# Proiect_TSC_v93.net
KiCad netlist of a schematic drawn in EAGLE
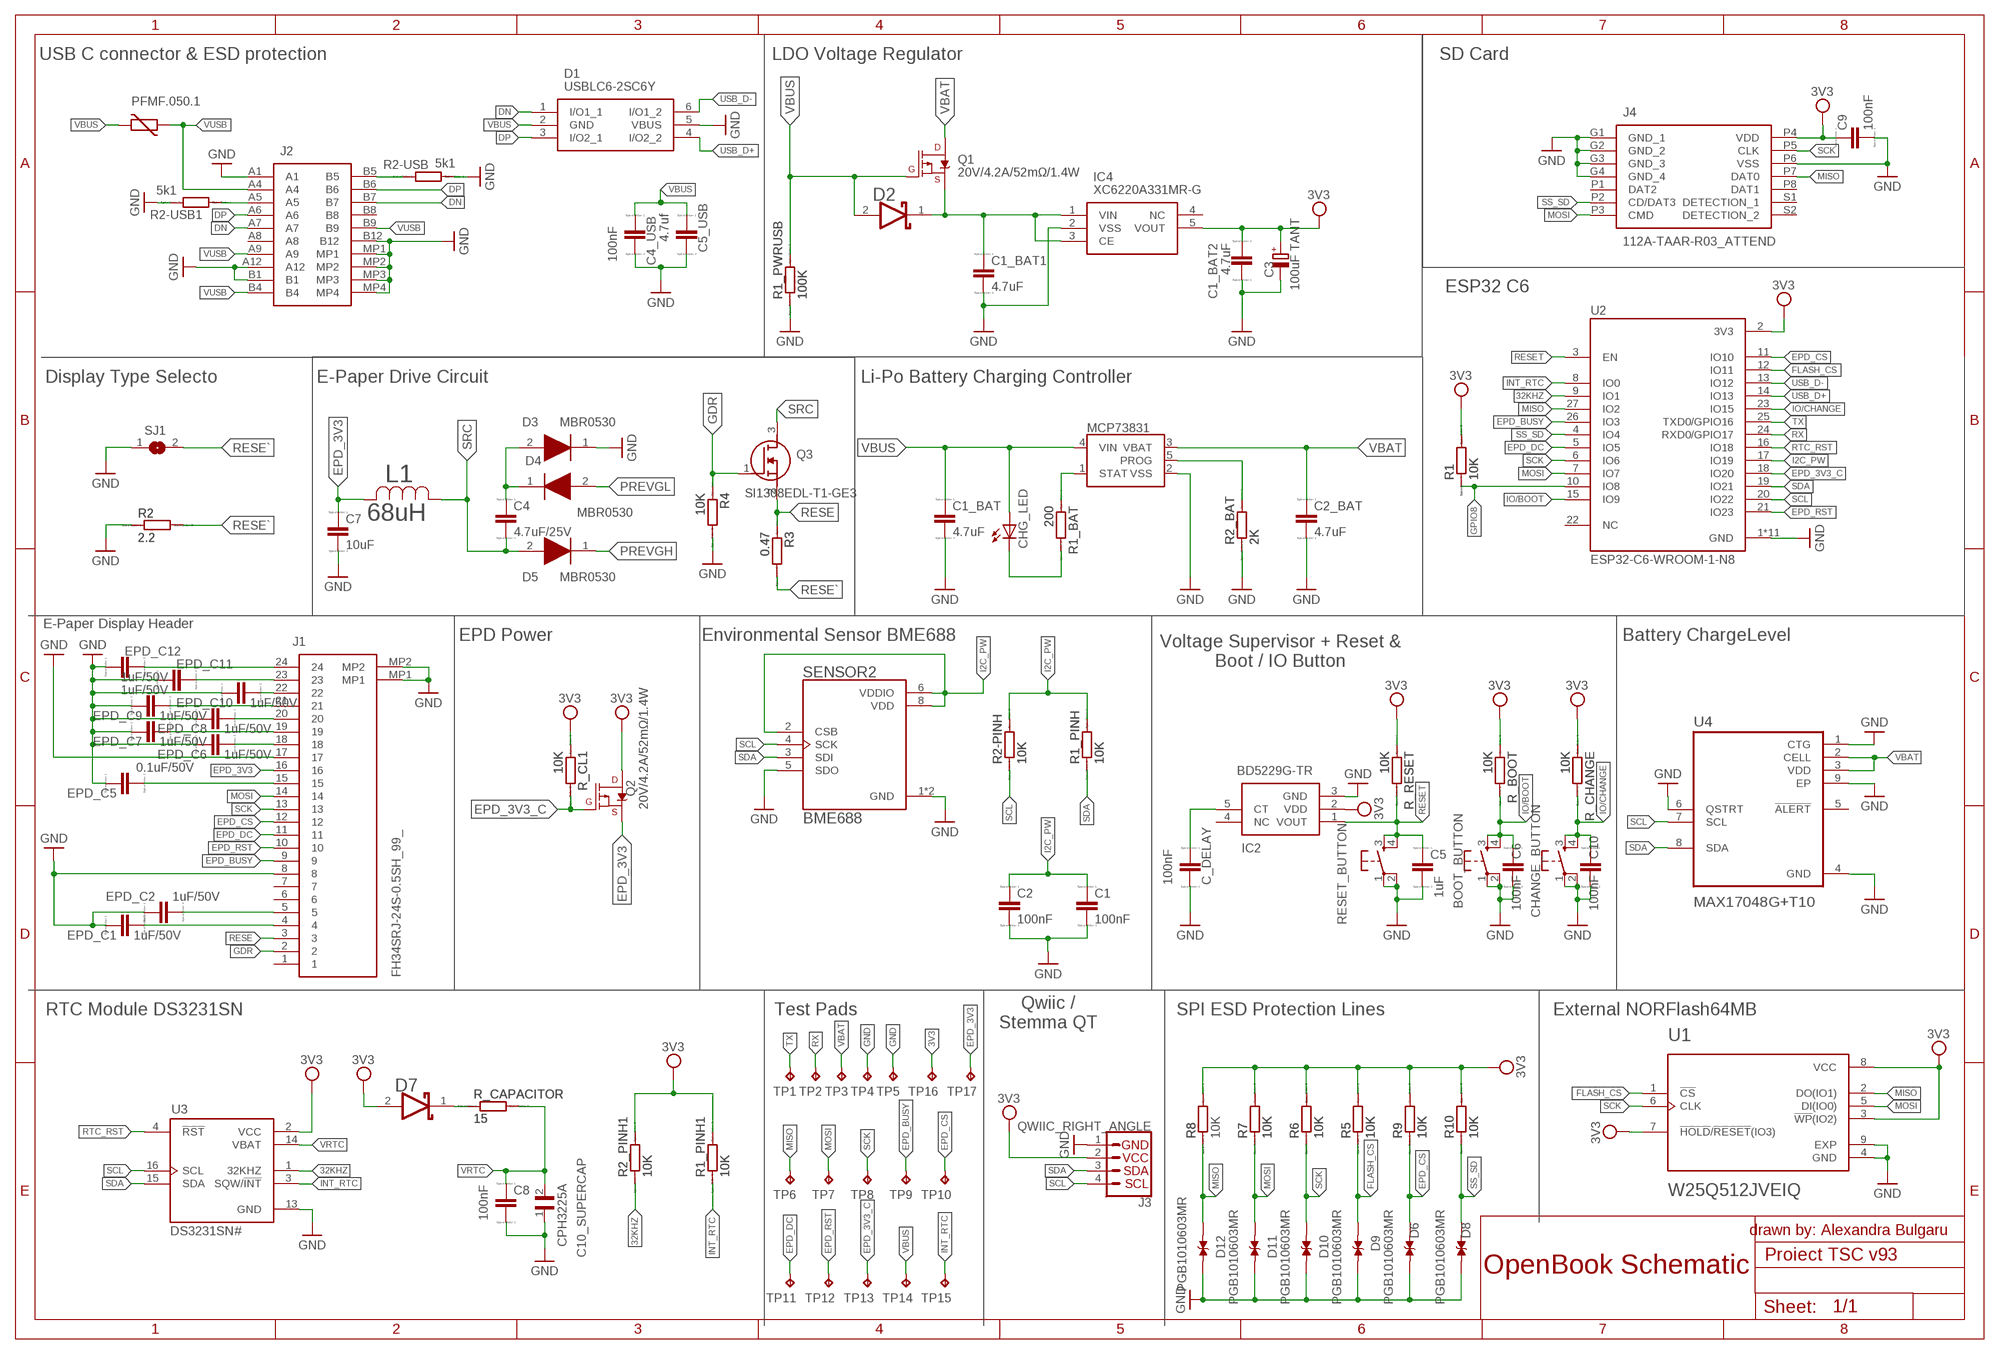
[diagram p0: schematic, sheet 1]

(export (version "E")
  (design (tool "Eeschema 10.0.6"))
  (components
    (comp (ref "BOOT_BUTTON")
      (value "BUTTON_CUSYOMV1")
      (footprint "eagle-import:MYBUTTON")
      (libsource (lib "eagle-import") (part "BUTTON_CUSYOMV1"))
    )
    (comp (ref "C1")
      (value "100nF")
      (footprint "eagle-import:EAGLE-LTSPICE_C0402")
      (libsource (lib "eagle-import") (part "EAGLE-LTSPICE_CC0402"))
    )
    (comp (ref "C1_BAT")
      (value "4.7uF")
      (footprint "eagle-import:EAGLE-LTSPICE_C0402")
      (libsource (lib "eagle-import") (part "EAGLE-LTSPICE_CC0402"))
    )
    (comp (ref "C1_BAT1")
      (value "4.7uF")
      (footprint "eagle-import:EAGLE-LTSPICE_C0402")
      (libsource (lib "eagle-import") (part "EAGLE-LTSPICE_CC0402"))
    )
    (comp (ref "C1_BAT2")
      (value "4.7uF")
      (footprint "eagle-import:EAGLE-LTSPICE_C0402")
      (libsource (lib "eagle-import") (part "EAGLE-LTSPICE_CC0402"))
    )
    (comp (ref "C2")
      (value "100nF")
      (footprint "eagle-import:EAGLE-LTSPICE_C0402")
      (libsource (lib "eagle-import") (part "EAGLE-LTSPICE_CC0402"))
    )
    (comp (ref "C2_BAT")
      (value "4.7uF")
      (footprint "eagle-import:EAGLE-LTSPICE_C0402")
      (libsource (lib "eagle-import") (part "EAGLE-LTSPICE_CC0402"))
    )
    (comp (ref "C3")
      (value "100uF TANT")
      (footprint "eagle-import:RCL_CT3528")
      (libsource (lib "eagle-import") (part "RCL_CPOL-EUCT3528"))
    )
    (comp (ref "C4")
      (value "4.7uF/25V")
      (footprint "eagle-import:EAGLE-LTSPICE_C0402")
      (libsource (lib "eagle-import") (part "EAGLE-LTSPICE_CC0402"))
    )
    (comp (ref "C4_USB")
      (value "100nF")
      (footprint "eagle-import:EAGLE-LTSPICE_C0402")
      (libsource (lib "eagle-import") (part "EAGLE-LTSPICE_CC0402"))
    )
    (comp (ref "C5")
      (value "1uF")
      (footprint "eagle-import:EAGLE-LTSPICE_C0402")
      (libsource (lib "eagle-import") (part "EAGLE-LTSPICE_CC0402"))
    )
    (comp (ref "C5_USB")
      (value "4.7uf")
      (footprint "eagle-import:EAGLE-LTSPICE_C0402")
      (libsource (lib "eagle-import") (part "EAGLE-LTSPICE_CC0402"))
    )
    (comp (ref "C6")
      (value "100nF")
      (footprint "eagle-import:EAGLE-LTSPICE_C0402")
      (libsource (lib "eagle-import") (part "EAGLE-LTSPICE_CC0402"))
    )
    (comp (ref "C7")
      (value "10uF")
      (footprint "eagle-import:EAGLE-LTSPICE_C0402")
      (libsource (lib "eagle-import") (part "EAGLE-LTSPICE_CC0402"))
    )
    (comp (ref "C8")
      (value "100nF")
      (footprint "eagle-import:EAGLE-LTSPICE_C0402")
      (libsource (lib "eagle-import") (part "EAGLE-LTSPICE_CC0402"))
    )
    (comp (ref "C9")
      (value "100nF")
      (footprint "eagle-import:ESP32_WROVER_EAGLE-LTSPICE_C0402")
      (libsource (lib "eagle-import") (part "ESP32_WROVER_EAGLE-LTSPICE_CC0402"))
    )
    (comp (ref "C10")
      (value "100nF")
      (footprint "eagle-import:EAGLE-LTSPICE_C0402")
      (libsource (lib "eagle-import") (part "EAGLE-LTSPICE_CC0402"))
    )
    (comp (ref "C10_SUPERCAP")
      (value "CPH3225A")
      (footprint "eagle-import:CAPCP3225X100N")
      (fields (field (name "MF") "Seiko Instruments"))
      (libsource (lib "eagle-import") (part "CPH3225A"))
    )
    (comp (ref "CHANGE_BUTTON")
      (value "BUTTON_CUSYOMV1")
      (footprint "eagle-import:MYBUTTON")
      (libsource (lib "eagle-import") (part "BUTTON_CUSYOMV1"))
    )
    (comp (ref "CHG_LED")
      (value "ADAFRUIT_LEDCHIP-LED0603")
      (footprint "eagle-import:ADAFRUIT_CHIP-LED0603")
      (libsource (lib "eagle-import") (part "ADAFRUIT_LEDCHIP-LED0603"))
    )
    (comp (ref "C_DELAY")
      (value "100nF")
      (footprint "eagle-import:EAGLE-LTSPICE_C0402")
      (libsource (lib "eagle-import") (part "EAGLE-LTSPICE_CC0402"))
    )
    (comp (ref "D1")
      (value "USBLC6-2SC6Y")
      (footprint "eagle-import:SOT95P280X145-6N")
      (fields (field (name "MF") "STMicroelectronics"))
      (libsource (lib "eagle-import") (part "USBLC6-2SC6Y"))
    )
    (comp (ref "D2")
      (value "ESP32_WROVER_AVX---SD0805S020S1R0_AVX_SD0805S020S1R0_0_0AVX_SD0805S020S1R0_0_0")
      (footprint "eagle-import:ESP32_WROVER_AVX---SD0805S020S1R0_AVX_SD0805S020S1R0_0")
      (fields
        (field (name "DIGIKEY_PART_NUMBER") "478-7800-1-ND")
        (field (name "MF") "AVX")
        (field (name "MOUSER_PART_NUMBER") "581-SD0805S020S1R0")
      )
      (libsource (lib "eagle-import") (part "ESP32_WROVER_AVX---SD0805S020S1R0_AVX_SD0805S020S1R0_0_0AVX_SD0805S020S1R0_0_0"))
    )
    (comp (ref "D3")
      (value "MBR0530")
      (footprint "eagle-import:SOD3716X135N")
      (fields (field (name "MF") "ON Semiconductor"))
      (libsource (lib "eagle-import") (part "MBR0530"))
    )
    (comp (ref "D4")
      (value "MBR0530")
      (footprint "eagle-import:SOD3716X135N")
      (fields (field (name "MF") "ON Semiconductor"))
      (libsource (lib "eagle-import") (part "MBR0530"))
    )
    (comp (ref "D5")
      (value "MBR0530")
      (footprint "eagle-import:SOD3716X135N")
      (fields (field (name "MF") "ON Semiconductor"))
      (libsource (lib "eagle-import") (part "MBR0530"))
    )
    (comp (ref "D6")
      (value "PGB1010603MR")
      (footprint "eagle-import:DIOC1608X36N")
      (fields (field (name "MF") "Littelfuse Inc."))
      (libsource (lib "eagle-import") (part "PGB1010603MR"))
    )
    (comp (ref "D7")
      (value "ESP32_WROVER_AVX---SD0805S020S1R0_AVX_SD0805S020S1R0_0_0AVX_SD0805S020S1R0_0_0")
      (footprint "eagle-import:ESP32_WROVER_AVX---SD0805S020S1R0_AVX_SD0805S020S1R0_0")
      (fields
        (field (name "DIGIKEY_PART_NUMBER") "478-7800-1-ND")
        (field (name "MF") "AVX")
        (field (name "MOUSER_PART_NUMBER") "581-SD0805S020S1R0")
      )
      (libsource (lib "eagle-import") (part "ESP32_WROVER_AVX---SD0805S020S1R0_AVX_SD0805S020S1R0_0_0AVX_SD0805S020S1R0_0_0"))
    )
    (comp (ref "D8")
      (value "PGB1010603MR")
      (footprint "eagle-import:DIOC1608X36N")
      (fields (field (name "MF") "Littelfuse Inc."))
      (libsource (lib "eagle-import") (part "PGB1010603MR"))
    )
    (comp (ref "D9")
      (value "PGB1010603MR")
      (footprint "eagle-import:DIOC1608X36N")
      (fields (field (name "MF") "Littelfuse Inc."))
      (libsource (lib "eagle-import") (part "PGB1010603MR"))
    )
    (comp (ref "D10")
      (value "PGB1010603MR")
      (footprint "eagle-import:DIOC1608X36N")
      (fields (field (name "MF") "Littelfuse Inc."))
      (libsource (lib "eagle-import") (part "PGB1010603MR"))
    )
    (comp (ref "D11")
      (value "PGB1010603MR")
      (footprint "eagle-import:DIOC1608X36N")
      (fields (field (name "MF") "Littelfuse Inc."))
      (libsource (lib "eagle-import") (part "PGB1010603MR"))
    )
    (comp (ref "D12")
      (value "PGB1010603MR")
      (footprint "eagle-import:DIOC1608X36N")
      (fields (field (name "MF") "Littelfuse Inc."))
      (libsource (lib "eagle-import") (part "PGB1010603MR"))
    )
    (comp (ref "EPD_C1")
      (value "1uF/50V")
      (footprint "eagle-import:EAGLE-LTSPICE_C0402")
      (libsource (lib "eagle-import") (part "EAGLE-LTSPICE_CC0402"))
    )
    (comp (ref "EPD_C2")
      (value "1uF/50V")
      (footprint "eagle-import:EAGLE-LTSPICE_C0402")
      (libsource (lib "eagle-import") (part "EAGLE-LTSPICE_CC0402"))
    )
    (comp (ref "EPD_C5")
      (value "0.1uF/50V")
      (footprint "eagle-import:EAGLE-LTSPICE_C0402")
      (libsource (lib "eagle-import") (part "EAGLE-LTSPICE_CC0402"))
    )
    (comp (ref "EPD_C6")
      (value "1uF/50V")
      (footprint "eagle-import:EAGLE-LTSPICE_C0402")
      (libsource (lib "eagle-import") (part "EAGLE-LTSPICE_CC0402"))
    )
    (comp (ref "EPD_C7")
      (value "1uF/50V")
      (footprint "eagle-import:EAGLE-LTSPICE_C0402")
      (libsource (lib "eagle-import") (part "EAGLE-LTSPICE_CC0402"))
    )
    (comp (ref "EPD_C8")
      (value "1uF/50V")
      (footprint "eagle-import:EAGLE-LTSPICE_C0402")
      (libsource (lib "eagle-import") (part "EAGLE-LTSPICE_CC0402"))
    )
    (comp (ref "EPD_C9")
      (value "1uF/50V")
      (footprint "eagle-import:EAGLE-LTSPICE_C0402")
      (libsource (lib "eagle-import") (part "EAGLE-LTSPICE_CC0402"))
    )
    (comp (ref "EPD_C10")
      (value "1uF/50V")
      (footprint "eagle-import:EAGLE-LTSPICE_C0402")
      (libsource (lib "eagle-import") (part "EAGLE-LTSPICE_CC0402"))
    )
    (comp (ref "EPD_C11")
      (value "1uF/50V")
      (footprint "eagle-import:EAGLE-LTSPICE_C0402")
      (libsource (lib "eagle-import") (part "EAGLE-LTSPICE_CC0402"))
    )
    (comp (ref "EPD_C12")
      (value "1uF/50V")
      (footprint "eagle-import:EAGLE-LTSPICE_C0402")
      (libsource (lib "eagle-import") (part "EAGLE-LTSPICE_CC0402"))
    )
    (comp (ref "IC2")
      (value "BD5229G-TR")
      (footprint "eagle-import:SOT95P280X125-5N")
      (fields (field (name "MOUSER_PART_NUMBER") "755-BD5229G-TR"))
      (libsource (lib "eagle-import") (part "BD5229G-TR"))
    )
    (comp (ref "IC4")
      (value "XC6220A331MR-G")
      (footprint "eagle-import:SOT95P280X120-5N")
      (fields (field (name "MOUSER_PART_NUMBER") "865-XC6220A331MR-G"))
      (libsource (lib "eagle-import") (part "XC6220A331MR-G"))
    )
    (comp (ref "J1")
      (value "FH34SRJ-24S-0.5SH_99_")
      (footprint "eagle-import:FH34SRJ24S05SH99")
      (fields
        (field (name "MANUFACTURER_PART_NUMBER") "FH34SRJ-24S-0.5SH(99)")
        (field (name "MOUSER_PART_NUMBER") "798-FH34SRJ24S05SH99")
      )
      (libsource (lib "eagle-import") (part "FH34SRJ-24S-0.5SH_99_"))
    )
    (comp (ref "J2")
      (value "SAMACSYS_PARTS_USB4110-GF-A")
      (footprint "eagle-import:SAMACSYS_PARTS_USB4110GFA")
      (fields
        (field (name "MANUFACTURER_PART_NUMBER") "USB4110-GF-A")
        (field (name "MOUSER_PART_NUMBER") "640-USB4110-GF-A")
      )
      (libsource (lib "eagle-import") (part "SAMACSYS_PARTS_USB4110-GF-A"))
    )
    (comp (ref "J3")
      (value "QWIIC_RIGHT_ANGLE")
      (footprint "eagle-import:JST04_1MM_RA")
      (libsource (lib "eagle-import") (part "QWIIC_CONNECTORJS-1MM"))
    )
    (comp (ref "J4")
      (value "112A-TAAR-R03_ATTEND")
      (footprint "eagle-import:112ATAARR03ATTEND")
      (fields (field (name "MANUFACTURER_PART_NUMBER") "112A-TAAR-R03 ATTEND"))
      (libsource (lib "eagle-import") (part "112A-TAAR-R03_ATTEND"))
    )
    (comp (ref "L1")
      (value "68uH")
      (footprint "eagle-import:IND_4828-WE-TPC_WRE")
      (fields
        (field (name "MANUFACTURER_PART_NUMBER") "744043680")
        (field (name "COPYRIGHT") "Copyright (C) 2024 Ultra Librarian. All rights reserved.")
      )
      (libsource (lib "eagle-import") (part "744043680IND_4828-WE-TPC_WRE"))
    )
    (comp (ref "MCP73831")
      (value "ESP32_WROVER_SPARKFUN-IC-POWER_MCP73831")
      (footprint "eagle-import:ESP32_WROVER_SPARKFUN-IC-POWER_SOT23-5")
      (libsource (lib "eagle-import") (part "ESP32_WROVER_SPARKFUN-IC-POWER_MCP73831"))
    )
    (comp (ref "PFMF.050.1")
      (value "ESP32C6_VARISTORCN1812")
      (footprint "eagle-import:ESP32C6_VARISTOR_CT_CN1812")
      (libsource (lib "eagle-import") (part "ESP32C6_VARISTORCN1812"))
    )
    (comp (ref "Q1")
      (value "20V/4.2A/52mΩ/1.4W")
      (footprint "eagle-import:ESP32_WROVER_SPARKFUN-DISCRETESEMI_SOT23-3")
      (libsource (lib "eagle-import") (part "ESP32_WROVER_SPARKFUN-DISCRETESEMI_MOSFET_PCH-DMG2305UX-7"))
    )
    (comp (ref "Q2")
      (value "20V/4.2A/52mΩ/1.4W")
      (footprint "eagle-import:ESP32_WROVER_SPARKFUN-DISCRETESEMI_SOT23-3")
      (libsource (lib "eagle-import") (part "ESP32_WROVER_SPARKFUN-DISCRETESEMI_MOSFET_PCH-DMG2305UX-7"))
    )
    (comp (ref "Q3")
      (value "SI1308EDL-T1-GE3")
      (footprint "eagle-import:SOT65P210X110-3N")
      (fields (field (name "MF") "Vishay Siliconix"))
      (libsource (lib "eagle-import") (part "SI1308EDL-T1-GE3"))
    )
    (comp (ref "R1")
      (value "10K")
      (footprint "eagle-import:ESP32_WROVER_EAGLE-LTSPICE_R0402")
      (libsource (lib "eagle-import") (part "ESP32_WROVER_EAGLE-LTSPICE_RR0402"))
    )
    (comp (ref "R1_BAT")
      (value "200")
      (footprint "eagle-import:ESP32_WROVER_EAGLE-LTSPICE_R0402")
      (libsource (lib "eagle-import") (part "ESP32_WROVER_EAGLE-LTSPICE_RR0402"))
    )
    (comp (ref "R1_PINH")
      (value "10K")
      (footprint "eagle-import:ESP32_WROVER_EAGLE-LTSPICE_R0402")
      (libsource (lib "eagle-import") (part "ESP32_WROVER_EAGLE-LTSPICE_RR0402"))
    )
    (comp (ref "R1_PINH1")
      (value "10K")
      (footprint "eagle-import:ESP32_WROVER_EAGLE-LTSPICE_R0402")
      (libsource (lib "eagle-import") (part "ESP32_WROVER_EAGLE-LTSPICE_RR0402"))
    )
    (comp (ref "R1_PWRUSB")
      (value "100K")
      (footprint "eagle-import:ESP32_WROVER_EAGLE-LTSPICE_R0402")
      (libsource (lib "eagle-import") (part "ESP32_WROVER_EAGLE-LTSPICE_RR0402"))
    )
    (comp (ref "R2")
      (value "2.2")
      (footprint "eagle-import:ESP32_WROVER_EAGLE-LTSPICE_R0402")
      (libsource (lib "eagle-import") (part "ESP32_WROVER_EAGLE-LTSPICE_RR0402"))
    )
    (comp (ref "R2-PINH")
      (value "10K")
      (footprint "eagle-import:ESP32_WROVER_EAGLE-LTSPICE_R0402")
      (libsource (lib "eagle-import") (part "ESP32_WROVER_EAGLE-LTSPICE_RR0402"))
    )
    (comp (ref "R2-USB")
      (value "5k1")
      (footprint "eagle-import:ESP32_WROVER_EAGLE-LTSPICE_R0402")
      (libsource (lib "eagle-import") (part "ESP32_WROVER_EAGLE-LTSPICE_RR0402"))
    )
    (comp (ref "R2-USB1")
      (value "5k1")
      (footprint "eagle-import:ESP32_WROVER_EAGLE-LTSPICE_R0402")
      (libsource (lib "eagle-import") (part "ESP32_WROVER_EAGLE-LTSPICE_RR0402"))
    )
    (comp (ref "R2_BAT")
      (value "2K")
      (footprint "eagle-import:ESP32_WROVER_EAGLE-LTSPICE_R0402")
      (libsource (lib "eagle-import") (part "ESP32_WROVER_EAGLE-LTSPICE_RR0402"))
    )
    (comp (ref "R2_PINH1")
      (value "10K")
      (footprint "eagle-import:ESP32_WROVER_EAGLE-LTSPICE_R0402")
      (libsource (lib "eagle-import") (part "ESP32_WROVER_EAGLE-LTSPICE_RR0402"))
    )
    (comp (ref "R3")
      (value "0.47")
      (footprint "eagle-import:ESP32_WROVER_EAGLE-LTSPICE_R0402")
      (libsource (lib "eagle-import") (part "ESP32_WROVER_EAGLE-LTSPICE_RR0402"))
    )
    (comp (ref "R4")
      (value "10K")
      (footprint "eagle-import:ESP32_WROVER_EAGLE-LTSPICE_R0402")
      (libsource (lib "eagle-import") (part "ESP32_WROVER_EAGLE-LTSPICE_RR0402"))
    )
    (comp (ref "R5")
      (value "10K")
      (footprint "eagle-import:ESP32_WROVER_EAGLE-LTSPICE_R0402")
      (libsource (lib "eagle-import") (part "ESP32_WROVER_EAGLE-LTSPICE_RR0402"))
    )
    (comp (ref "R6")
      (value "10K")
      (footprint "eagle-import:ESP32_WROVER_EAGLE-LTSPICE_R0402")
      (libsource (lib "eagle-import") (part "ESP32_WROVER_EAGLE-LTSPICE_RR0402"))
    )
    (comp (ref "R7")
      (value "10K")
      (footprint "eagle-import:ESP32_WROVER_EAGLE-LTSPICE_R0402")
      (libsource (lib "eagle-import") (part "ESP32_WROVER_EAGLE-LTSPICE_RR0402"))
    )
    (comp (ref "R8")
      (value "10K")
      (footprint "eagle-import:ESP32_WROVER_EAGLE-LTSPICE_R0402")
      (libsource (lib "eagle-import") (part "ESP32_WROVER_EAGLE-LTSPICE_RR0402"))
    )
    (comp (ref "R9")
      (value "10K")
      (footprint "eagle-import:ESP32_WROVER_EAGLE-LTSPICE_R0402")
      (libsource (lib "eagle-import") (part "ESP32_WROVER_EAGLE-LTSPICE_RR0402"))
    )
    (comp (ref "R10")
      (value "10K")
      (footprint "eagle-import:ESP32_WROVER_EAGLE-LTSPICE_R0402")
      (libsource (lib "eagle-import") (part "ESP32_WROVER_EAGLE-LTSPICE_RR0402"))
    )
    (comp (ref "RESET_BUTTON")
      (value "BUTTON_CUSYOMV1")
      (footprint "eagle-import:MYBUTTON")
      (libsource (lib "eagle-import") (part "BUTTON_CUSYOMV1"))
    )
    (comp (ref "R_BOOT")
      (value "10K")
      (footprint "eagle-import:ESP32_WROVER_EAGLE-LTSPICE_R0402")
      (libsource (lib "eagle-import") (part "ESP32_WROVER_EAGLE-LTSPICE_RR0402"))
    )
    (comp (ref "R_CAPACITOR")
      (value "15")
      (footprint "eagle-import:ESP32_WROVER_EAGLE-LTSPICE_R0402")
      (libsource (lib "eagle-import") (part "ESP32_WROVER_EAGLE-LTSPICE_RR0402"))
    )
    (comp (ref "R_CHANGE")
      (value "10K")
      (footprint "eagle-import:ESP32_WROVER_EAGLE-LTSPICE_R0402")
      (libsource (lib "eagle-import") (part "ESP32_WROVER_EAGLE-LTSPICE_RR0402"))
    )
    (comp (ref "R_CL1")
      (value "10K")
      (footprint "eagle-import:ESP32_WROVER_EAGLE-LTSPICE_R0402")
      (libsource (lib "eagle-import") (part "ESP32_WROVER_EAGLE-LTSPICE_RR0402"))
    )
    (comp (ref "R_RESET")
      (value "10K")
      (footprint "eagle-import:ESP32_WROVER_EAGLE-LTSPICE_R0402")
      (libsource (lib "eagle-import") (part "ESP32_WROVER_EAGLE-LTSPICE_RR0402"))
    )
    (comp (ref "SENSOR2")
      (value "BME688")
      (footprint "eagle-import:ESP32_WROVER_BME680_PSON80P300X300X100-8N")
      (fields (field (name "MF") "Bosch Sensortec") (field (name "MP") "BME680"))
      (libsource (lib "eagle-import") (part "ESP32_WROVER_BME680_BME680"))
    )
    (comp (ref "SJ1") (value "SJ") (footprint "eagle-import:SJ") (libsource (lib "eagle-import") (part "SJ")))
    (comp (ref "TP1")
      (value "TPTP20R")
      (footprint "eagle-import:TP20R")
      (libsource (lib "eagle-import") (part "TPTP20R"))
    )
    (comp (ref "TP2")
      (value "TPTP20R")
      (footprint "eagle-import:TP20R")
      (libsource (lib "eagle-import") (part "TPTP20R"))
    )
    (comp (ref "TP3")
      (value "TPTP20R")
      (footprint "eagle-import:TP20R")
      (libsource (lib "eagle-import") (part "TPTP20R"))
    )
    (comp (ref "TP4")
      (value "TPTP20R")
      (footprint "eagle-import:TP20R")
      (libsource (lib "eagle-import") (part "TPTP20R"))
    )
    (comp (ref "TP5")
      (value "TPTP20R")
      (footprint "eagle-import:TP20R")
      (libsource (lib "eagle-import") (part "TPTP20R"))
    )
    (comp (ref "TP6")
      (value "TPTP20R")
      (footprint "eagle-import:TP20R")
      (libsource (lib "eagle-import") (part "TPTP20R"))
    )
    (comp (ref "TP7")
      (value "TPTP20R")
      (footprint "eagle-import:TP20R")
      (libsource (lib "eagle-import") (part "TPTP20R"))
    )
    (comp (ref "TP8")
      (value "TPTP20R")
      (footprint "eagle-import:TP20R")
      (libsource (lib "eagle-import") (part "TPTP20R"))
    )
    (comp (ref "TP9")
      (value "TPTP20R")
      (footprint "eagle-import:TP20R")
      (libsource (lib "eagle-import") (part "TPTP20R"))
    )
    (comp (ref "TP10")
      (value "TPTP20R")
      (footprint "eagle-import:TP20R")
      (libsource (lib "eagle-import") (part "TPTP20R"))
    )
    (comp (ref "TP11")
      (value "TPTP20R")
      (footprint "eagle-import:TP20R")
      (libsource (lib "eagle-import") (part "TPTP20R"))
    )
    (comp (ref "TP12")
      (value "TPTP20R")
      (footprint "eagle-import:TP20R")
      (libsource (lib "eagle-import") (part "TPTP20R"))
    )
    (comp (ref "TP13")
      (value "TPTP20R")
      (footprint "eagle-import:TP20R")
      (libsource (lib "eagle-import") (part "TPTP20R"))
    )
    (comp (ref "TP14")
      (value "TPTP20R")
      (footprint "eagle-import:TP20R")
      (libsource (lib "eagle-import") (part "TPTP20R"))
    )
    (comp (ref "TP15")
      (value "TPTP20R")
      (footprint "eagle-import:TP20R")
      (libsource (lib "eagle-import") (part "TPTP20R"))
    )
    (comp (ref "TP16")
      (value "TPTP20R")
      (footprint "eagle-import:TP20R")
      (libsource (lib "eagle-import") (part "TPTP20R"))
    )
    (comp (ref "TP17")
      (value "TPTP20R")
      (footprint "eagle-import:TP20R")
      (libsource (lib "eagle-import") (part "TPTP20R"))
    )
    (comp (ref "U1")
      (value "W25Q512JVEIQ")
      (footprint "eagle-import:SON127P600X800X80-9N")
      (fields (field (name "MF") "Winbond Electronics"))
      (libsource (lib "eagle-import") (part "W25Q512JVEIQ"))
    )
    (comp (ref "U2")
      (value "ESP32-C6-WROOM-1-N8")
      (footprint "eagle-import:XCVR_ESP32-C6-WROOM-1-N8")
      (fields (field (name "MF") "Espressif Systems"))
      (libsource (lib "eagle-import") (part "ESP32-C6-WROOM-1-N8"))
    )
    (comp (ref "U3")
      (value "DS3231SN#")
      (footprint "eagle-import:SOIC127P1032X265-16N")
      (fields (field (name "MF") "Analog Devices"))
      (libsource (lib "eagle-import") (part "DS3231SN#"))
    )
    (comp (ref "U4")
      (value "MAX17048G+T10")
      (footprint "eagle-import:SON50P200X200X80-9N")
      (fields (field (name "MF") "Analog Devices"))
      (libsource (lib "eagle-import") (part "MAX17048G+T10"))
    )
  )
  (nets
    (net (code "1") (name "3V3") (class "Default")
      (node (ref "C1_BAT2") (pin "2") (pinfunction "2_2") (pintype "passive"))
      (node (ref "C3") (pin "+") (pinfunction "+_+") (pintype "passive"))
      (node (ref "C9") (pin "1") (pinfunction "1_1") (pintype "passive"))
      (node (ref "D7") (pin "2") (pinfunction "ANODE_2") (pintype "bidirectional"))
      (node (ref "IC2") (pin "2") (pinfunction "VDD_2") (pintype "bidirectional"))
      (node (ref "IC4") (pin "5") (pinfunction "VOUT_5") (pintype "bidirectional"))
      (node (ref "J3") (pin "2") (pinfunction "2_2") (pintype "power_in"))
      (node (ref "J4") (pin "P4") (pinfunction "VDD_P4") (pintype "bidirectional"))
      (node (ref "Q2") (pin "3") (pinfunction "D_3") (pintype "bidirectional"))
      (node (ref "R1") (pin "2") (pinfunction "2_2") (pintype "passive"))
      (node (ref "R10") (pin "2") (pinfunction "2_2") (pintype "passive"))
      (node (ref "R1_PINH1") (pin "2") (pinfunction "2_2") (pintype "passive"))
      (node (ref "R2_PINH1") (pin "2") (pinfunction "2_2") (pintype "passive"))
      (node (ref "R5") (pin "2") (pinfunction "2_2") (pintype "passive"))
      (node (ref "R6") (pin "2") (pinfunction "2_2") (pintype "passive"))
      (node (ref "R7") (pin "2") (pinfunction "2_2") (pintype "passive"))
      (node (ref "R8") (pin "2") (pinfunction "2_2") (pintype "passive"))
      (node (ref "R9") (pin "2") (pinfunction "2_2") (pintype "passive"))
      (node (ref "R_BOOT") (pin "1") (pinfunction "1_1") (pintype "passive"))
      (node (ref "R_CHANGE") (pin "1") (pinfunction "1_1") (pintype "passive"))
      (node (ref "R_CL1") (pin "1") (pinfunction "1_1") (pintype "passive"))
      (node (ref "R_RESET") (pin "1") (pinfunction "1_1") (pintype "passive"))
      (node (ref "TP16") (pin "TP") (pinfunction "TP_TP") (pintype "input"))
      (node (ref "U1") (pin "3") (pinfunction "~{WP}(IO2)_3") (pintype "bidirectional"))
      (node (ref "U1") (pin "7") (pinfunction "~{HOLD}/~{RESET}(IO3)_7") (pintype "bidirectional"))
      (node (ref "U1") (pin "8") (pinfunction "VCC_8") (pintype "power_in"))
      (node (ref "U2") (pin "2") (pinfunction "3V3_2") (pintype "power_in"))
      (node (ref "U3") (pin "2") (pinfunction "VCC_2") (pintype "power_in"))
    )
    (net (code "2") (name "32KHZ") (class "Default")
      (node (ref "R2_PINH1") (pin "1") (pinfunction "1_1") (pintype "passive"))
      (node (ref "U2") (pin "9") (pinfunction "IO1_9") (pintype "bidirectional"))
      (node (ref "U3") (pin "1") (pinfunction "32KHZ_1") (pintype "output"))
    )
    (net (code "3") (name "DN") (class "Default")
      (node (ref "D1") (pin "1") (pinfunction "I/O1_1_1") (pintype "bidirectional"))
      (node (ref "J2") (pin "A7") (pinfunction "A7_A7") (pintype "bidirectional"))
      (node (ref "J2") (pin "B7") (pinfunction "B7_B7") (pintype "bidirectional"))
    )
    (net (code "4") (name "DP") (class "Default")
      (node (ref "D1") (pin "3") (pinfunction "I/O2_1_3") (pintype "bidirectional"))
      (node (ref "J2") (pin "A6") (pinfunction "A6_A6") (pintype "bidirectional"))
      (node (ref "J2") (pin "B6") (pinfunction "B6_B6") (pintype "bidirectional"))
    )
    (net (code "5") (name "EPD_3V3") (class "Default")
      (node (ref "C7") (pin "1") (pinfunction "1_1") (pintype "passive"))
      (node (ref "J1") (pin "16") (pinfunction "16_16") (pintype "bidirectional"))
      (node (ref "L1") (pin "2") (pinfunction "2_2") (pintype "passive"))
      (node (ref "Q2") (pin "2") (pinfunction "S_2") (pintype "bidirectional"))
      (node (ref "TP17") (pin "TP") (pinfunction "TP_TP") (pintype "input"))
    )
    (net (code "6") (name "EPD_3V3_C") (class "Default")
      (node (ref "Q2") (pin "1") (pinfunction "G_1") (pintype "bidirectional"))
      (node (ref "R_CL1") (pin "2") (pinfunction "2_2") (pintype "passive"))
      (node (ref "TP13") (pin "TP") (pinfunction "TP_TP") (pintype "input"))
      (node (ref "U2") (pin "18") (pinfunction "IO20_18") (pintype "bidirectional"))
    )
    (net (code "7") (name "EPD_BUSY") (class "Default")
      (node (ref "J1") (pin "9") (pinfunction "9_9") (pintype "bidirectional"))
      (node (ref "TP9") (pin "TP") (pinfunction "TP_TP") (pintype "input"))
      (node (ref "U2") (pin "26") (pinfunction "IO3_26") (pintype "bidirectional"))
    )
    (net (code "8") (name "EPD_CS") (class "Default")
      (node (ref "D6") (pin "1") (pinfunction "1_1") (pintype "passive"))
      (node (ref "J1") (pin "12") (pinfunction "12_12") (pintype "bidirectional"))
      (node (ref "R9") (pin "1") (pinfunction "1_1") (pintype "passive"))
      (node (ref "TP10") (pin "TP") (pinfunction "TP_TP") (pintype "input"))
      (node (ref "U2") (pin "11") (pinfunction "IO10_11") (pintype "bidirectional"))
    )
    (net (code "9") (name "EPD_DC") (class "Default")
      (node (ref "J1") (pin "11") (pinfunction "11_11") (pintype "bidirectional"))
      (node (ref "TP11") (pin "TP") (pinfunction "TP_TP") (pintype "input"))
      (node (ref "U2") (pin "5") (pinfunction "IO5_5") (pintype "bidirectional"))
    )
    (net (code "10") (name "EPD_RST") (class "Default")
      (node (ref "J1") (pin "10") (pinfunction "10_10") (pintype "bidirectional"))
      (node (ref "TP12") (pin "TP") (pinfunction "TP_TP") (pintype "input"))
      (node (ref "U2") (pin "21") (pinfunction "IO23_21") (pintype "bidirectional"))
    )
    (net (code "11") (name "FLASH_CS") (class "Default")
      (node (ref "D9") (pin "1") (pinfunction "1_1") (pintype "passive"))
      (node (ref "R5") (pin "1") (pinfunction "1_1") (pintype "passive"))
      (node (ref "U1") (pin "1") (pinfunction "~{CS}_1") (pintype "input"))
      (node (ref "U2") (pin "12") (pinfunction "IO11_12") (pintype "bidirectional"))
    )
    (net (code "12") (name "GDR") (class "Default")
      (node (ref "J1") (pin "2") (pinfunction "2_2") (pintype "bidirectional"))
      (node (ref "Q3") (pin "1") (pinfunction "G_1") (pintype "bidirectional"))
      (node (ref "R4") (pin "1") (pinfunction "1_1") (pintype "passive"))
    )
    (net (code "13") (name "GND") (class "Default")
      (node (ref "BOOT_BUTTON") (pin "1") (pinfunction "1_1") (pintype "passive"))
      (node (ref "BOOT_BUTTON") (pin "2") (pinfunction "2_2") (pintype "passive"))
      (node (ref "C1") (pin "2") (pinfunction "2_2") (pintype "passive"))
      (node (ref "C10") (pin "2") (pinfunction "2_2") (pintype "passive"))
      (node (ref "C10_SUPERCAP") (pin "1") (pinfunction "1_1") (pintype "passive"))
      (node (ref "C1_BAT") (pin "2") (pinfunction "2_2") (pintype "passive"))
      (node (ref "C1_BAT1") (pin "2") (pinfunction "2_2") (pintype "passive"))
      (node (ref "C1_BAT2") (pin "1") (pinfunction "1_1") (pintype "passive"))
      (node (ref "C2") (pin "2") (pinfunction "2_2") (pintype "passive"))
      (node (ref "C2_BAT") (pin "2") (pinfunction "2_2") (pintype "passive"))
      (node (ref "C3") (pin "-") (pinfunction "-_-") (pintype "passive"))
      (node (ref "C4_USB") (pin "2") (pinfunction "2_2") (pintype "passive"))
      (node (ref "C5") (pin "2") (pinfunction "2_2") (pintype "passive"))
      (node (ref "C5_USB") (pin "2") (pinfunction "2_2") (pintype "passive"))
      (node (ref "C6") (pin "2") (pinfunction "2_2") (pintype "passive"))
      (node (ref "C7") (pin "2") (pinfunction "2_2") (pintype "passive"))
      (node (ref "C8") (pin "2") (pinfunction "2_2") (pintype "passive"))
      (node (ref "C9") (pin "2") (pinfunction "2_2") (pintype "passive"))
      (node (ref "CHANGE_BUTTON") (pin "1") (pinfunction "1_1") (pintype "passive"))
      (node (ref "CHANGE_BUTTON") (pin "2") (pinfunction "2_2") (pintype "passive"))
      (node (ref "C_DELAY") (pin "2") (pinfunction "2_2") (pintype "passive"))
      (node (ref "D1") (pin "5") (pinfunction "VBUS_5") (pintype "bidirectional"))
      (node (ref "D10") (pin "2") (pinfunction "2_2") (pintype "passive"))
      (node (ref "D11") (pin "2") (pinfunction "2_2") (pintype "passive"))
      (node (ref "D12") (pin "2") (pinfunction "2_2") (pintype "passive"))
      (node (ref "D3") (pin "1") (pinfunction "K_1") (pintype "bidirectional"))
      (node (ref "D6") (pin "2") (pinfunction "2_2") (pintype "passive"))
      (node (ref "D8") (pin "2") (pinfunction "2_2") (pintype "passive"))
      (node (ref "D9") (pin "2") (pinfunction "2_2") (pintype "passive"))
      (node (ref "EPD_C1") (pin "1") (pinfunction "1_1") (pintype "passive"))
      (node (ref "EPD_C10") (pin "1") (pinfunction "1_1") (pintype "passive"))
      (node (ref "EPD_C11") (pin "1") (pinfunction "1_1") (pintype "passive"))
      (node (ref "EPD_C11") (pin "2") (pinfunction "2_2") (pintype "passive"))
      (node (ref "EPD_C12") (pin "1") (pinfunction "1_1") (pintype "passive"))
      (node (ref "EPD_C2") (pin "1") (pinfunction "1_1") (pintype "passive"))
      (node (ref "EPD_C5") (pin "1") (pinfunction "1_1") (pintype "passive"))
      (node (ref "EPD_C6") (pin "1") (pinfunction "1_1") (pintype "passive"))
      (node (ref "EPD_C7") (pin "1") (pinfunction "1_1") (pintype "passive"))
      (node (ref "EPD_C8") (pin "1") (pinfunction "1_1") (pintype "passive"))
      (node (ref "EPD_C9") (pin "1") (pinfunction "1_1") (pintype "passive"))
      (node (ref "IC2") (pin "3") (pinfunction "GND_3") (pintype "bidirectional"))
      (node (ref "IC4") (pin "2") (pinfunction "VSS_2") (pintype "bidirectional"))
      (node (ref "J1") (pin "17") (pinfunction "17_17") (pintype "bidirectional"))
      (node (ref "J1") (pin "23") (pinfunction "23_23") (pintype "bidirectional"))
      (node (ref "J1") (pin "8") (pinfunction "8_8") (pintype "bidirectional"))
      (node (ref "J1") (pin "MP1") (pinfunction "MP1_MP1") (pintype "bidirectional"))
      (node (ref "J1") (pin "MP2") (pinfunction "MP2_MP2") (pintype "bidirectional"))
      (node (ref "J2") (pin "A1") (pinfunction "A1_A1") (pintype "bidirectional"))
      (node (ref "J2") (pin "A12") (pinfunction "A12_A12") (pintype "bidirectional"))
      (node (ref "J2") (pin "B1") (pinfunction "B1_B1") (pintype "bidirectional"))
      (node (ref "J2") (pin "B12") (pinfunction "B12_B12") (pintype "bidirectional"))
      (node (ref "J2") (pin "MP1") (pinfunction "MP1_MP1") (pintype "bidirectional"))
      (node (ref "J2") (pin "MP2") (pinfunction "MP2_MP2") (pintype "bidirectional"))
      (node (ref "J2") (pin "MP3") (pinfunction "MP3_MP3") (pintype "bidirectional"))
      (node (ref "J2") (pin "MP4") (pinfunction "MP4_MP4") (pintype "bidirectional"))
      (node (ref "J3") (pin "1") (pinfunction "1_1") (pintype "power_in"))
      (node (ref "J4") (pin "G1") (pinfunction "GND_1_G1") (pintype "bidirectional"))
      (node (ref "J4") (pin "G2") (pinfunction "GND_2_G2") (pintype "bidirectional"))
      (node (ref "J4") (pin "G3") (pinfunction "GND_3_G3") (pintype "bidirectional"))
      (node (ref "J4") (pin "G4") (pinfunction "GND_4_G4") (pintype "bidirectional"))
      (node (ref "J4") (pin "P6") (pinfunction "VSS_P6") (pintype "bidirectional"))
      (node (ref "MCP73831") (pin "2") (pinfunction "VSS_2") (pintype "power_in"))
      (node (ref "R1_PWRUSB") (pin "1") (pinfunction "1_1") (pintype "passive"))
      (node (ref "R2") (pin "1") (pinfunction "1_1") (pintype "passive"))
      (node (ref "R2-USB") (pin "2") (pinfunction "2_2") (pintype "passive"))
      (node (ref "R2-USB1") (pin "2") (pinfunction "2_2") (pintype "passive"))
      (node (ref "R2_BAT") (pin "1") (pinfunction "1_1") (pintype "passive"))
      (node (ref "R4") (pin "2") (pinfunction "2_2") (pintype "passive"))
      (node (ref "RESET_BUTTON") (pin "1") (pinfunction "1_1") (pintype "passive"))
      (node (ref "RESET_BUTTON") (pin "2") (pinfunction "2_2") (pintype "passive"))
      (node (ref "SENSOR2") (pin "1") (pinfunction "GND_1") (pintype "power_in"))
      (node (ref "SENSOR2") (pin "5") (pinfunction "SDO_5") (pintype "bidirectional"))
      (node (ref "SENSOR2") (pin "7") (pinfunction "GND_7") (pintype "power_in"))
      (node (ref "SJ1") (pin "1") (pinfunction "1_1") (pintype "passive"))
      (node (ref "TP4") (pin "TP") (pinfunction "TP_TP") (pintype "input"))
      (node (ref "TP5") (pin "TP") (pinfunction "TP_TP") (pintype "input"))
      (node (ref "U1") (pin "4") (pinfunction "GND_4") (pintype "power_in"))
      (node (ref "U1") (pin "9") (pinfunction "EXP_9") (pintype "passive"))
      (node (ref "U2") (pin "1") (pinfunction "GND_1") (pintype "power_in"))
      (node (ref "U2") (pin "28") (pinfunction "GND_28") (pintype "power_in"))
      (node (ref "U2") (pin "29_1") (pinfunction "GND_29_1") (pintype "power_in"))
      (node (ref "U2") (pin "29_2") (pinfunction "GND_29_2") (pintype "power_in"))
      (node (ref "U2") (pin "29_3") (pinfunction "GND_29_3") (pintype "power_in"))
      (node (ref "U2") (pin "29_4") (pinfunction "GND_29_4") (pintype "power_in"))
      (node (ref "U2") (pin "29_5") (pinfunction "GND_29_5") (pintype "power_in"))
      (node (ref "U2") (pin "29_6") (pinfunction "GND_29_6") (pintype "power_in"))
      (node (ref "U2") (pin "29_7") (pinfunction "GND_29_7") (pintype "power_in"))
      (node (ref "U2") (pin "29_8") (pinfunction "GND_29_8") (pintype "power_in"))
      (node (ref "U2") (pin "29_9") (pinfunction "GND_29_9") (pintype "power_in"))
      (node (ref "U3") (pin "13") (pinfunction "GND_13") (pintype "power_in"))
      (node (ref "U4") (pin "1") (pinfunction "CTG_1") (pintype "power_in"))
      (node (ref "U4") (pin "4") (pinfunction "GND_4") (pintype "power_in"))
      (node (ref "U4") (pin "6") (pinfunction "QSTRT_6") (pintype "input"))
      (node (ref "U4") (pin "9") (pinfunction "EP_9") (pintype "power_in"))
    )
    (net (code "14") (name "GPIO8") (class "Default")
      (node (ref "R1") (pin "1") (pinfunction "1_1") (pintype "passive"))
      (node (ref "U2") (pin "10") (pinfunction "IO8_10") (pintype "bidirectional"))
    )
    (net (code "15") (name "I2C_PW") (class "Default")
      (node (ref "C1") (pin "1") (pinfunction "1_1") (pintype "passive"))
      (node (ref "C2") (pin "1") (pinfunction "1_1") (pintype "passive"))
      (node (ref "R1_PINH") (pin "2") (pinfunction "2_2") (pintype "passive"))
      (node (ref "R2-PINH") (pin "2") (pinfunction "2_2") (pintype "passive"))
      (node (ref "SENSOR2") (pin "2") (pinfunction "CSB_2") (pintype "input"))
      (node (ref "SENSOR2") (pin "6") (pinfunction "VDDIO_6") (pintype "power_in"))
      (node (ref "SENSOR2") (pin "8") (pinfunction "VDD_8") (pintype "power_in"))
      (node (ref "U2") (pin "17") (pinfunction "IO19_17") (pintype "bidirectional"))
    )
    (net (code "16") (name "INT_RTC") (class "Default")
      (node (ref "R1_PINH1") (pin "1") (pinfunction "1_1") (pintype "passive"))
      (node (ref "TP15") (pin "TP") (pinfunction "TP_TP") (pintype "input"))
      (node (ref "U2") (pin "8") (pinfunction "IO0_8") (pintype "bidirectional"))
      (node (ref "U3") (pin "3") (pinfunction "SQW/~{INT}_3") (pintype "output"))
    )
    (net (code "17") (name "IO{slash}BOOT") (class "Default")
      (node (ref "BOOT_BUTTON") (pin "3") (pinfunction "3_3") (pintype "passive"))
      (node (ref "BOOT_BUTTON") (pin "4") (pinfunction "4_4") (pintype "passive"))
      (node (ref "C6") (pin "1") (pinfunction "1_1") (pintype "passive"))
      (node (ref "R_BOOT") (pin "2") (pinfunction "2_2") (pintype "passive"))
      (node (ref "U2") (pin "15") (pinfunction "IO9_15") (pintype "bidirectional"))
    )
    (net (code "18") (name "IO{slash}CHANGE") (class "Default")
      (node (ref "C10") (pin "1") (pinfunction "1_1") (pintype "passive"))
      (node (ref "CHANGE_BUTTON") (pin "3") (pinfunction "3_3") (pintype "passive"))
      (node (ref "CHANGE_BUTTON") (pin "4") (pinfunction "4_4") (pintype "passive"))
      (node (ref "R_CHANGE") (pin "2") (pinfunction "2_2") (pintype "passive"))
      (node (ref "U2") (pin "23") (pinfunction "IO15_23") (pintype "bidirectional"))
    )
    (net (code "19") (name "MISO") (class "Default")
      (node (ref "D12") (pin "1") (pinfunction "1_1") (pintype "passive"))
      (node (ref "J4") (pin "P7") (pinfunction "DAT0_P7") (pintype "bidirectional"))
      (node (ref "R8") (pin "1") (pinfunction "1_1") (pintype "passive"))
      (node (ref "TP6") (pin "TP") (pinfunction "TP_TP") (pintype "input"))
      (node (ref "U1") (pin "2") (pinfunction "DO(IO1)_2") (pintype "bidirectional"))
      (node (ref "U2") (pin "27") (pinfunction "IO2_27") (pintype "bidirectional"))
    )
    (net (code "20") (name "MOSI") (class "Default")
      (node (ref "D11") (pin "1") (pinfunction "1_1") (pintype "passive"))
      (node (ref "J1") (pin "14") (pinfunction "14_14") (pintype "bidirectional"))
      (node (ref "J4") (pin "P3") (pinfunction "CMD_P3") (pintype "bidirectional"))
      (node (ref "R7") (pin "1") (pinfunction "1_1") (pintype "passive"))
      (node (ref "TP7") (pin "TP") (pinfunction "TP_TP") (pintype "input"))
      (node (ref "U1") (pin "5") (pinfunction "DI(IO0)_5") (pintype "bidirectional"))
      (node (ref "U2") (pin "7") (pinfunction "IO7_7") (pintype "bidirectional"))
    )
    (net (code "21") (name "Net-(CHG_LED-PadC)") (class "Default")
      (node (ref "CHG_LED") (pin "C") (pinfunction "C_C") (pintype "passive"))
      (node (ref "R1_BAT") (pin "2") (pinfunction "2_2") (pintype "passive"))
    )
    (net (code "22") (name "Net-(D2-CATHODE)") (class "Default")
      (node (ref "C1_BAT1") (pin "1") (pinfunction "1_1") (pintype "passive"))
      (node (ref "D2") (pin "1") (pinfunction "CATHODE_1") (pintype "bidirectional"))
      (node (ref "IC4") (pin "1") (pinfunction "VIN_1") (pintype "bidirectional"))
      (node (ref "IC4") (pin "3") (pinfunction "CE_3") (pintype "bidirectional"))
      (node (ref "Q1") (pin "2") (pinfunction "S_2") (pintype "bidirectional"))
    )
    (net (code "23") (name "Net-(D3-A)") (class "Default")
      (node (ref "C4") (pin "1") (pinfunction "1_1") (pintype "passive"))
      (node (ref "D3") (pin "2") (pinfunction "A_2") (pintype "bidirectional"))
      (node (ref "D4") (pin "1") (pinfunction "K_1") (pintype "bidirectional"))
    )
    (net (code "24") (name "Net-(D7-CATHODE)") (class "Default")
      (node (ref "D7") (pin "1") (pinfunction "CATHODE_1") (pintype "bidirectional"))
      (node (ref "R_CAPACITOR") (pin "1") (pinfunction "1_1") (pintype "passive"))
    )
    (net (code "25") (name "Net-(EPD_C1-Pad2)") (class "Default")
      (node (ref "EPD_C1") (pin "2") (pinfunction "2_2") (pintype "passive"))
      (node (ref "J1") (pin "4") (pinfunction "4_4") (pintype "bidirectional"))
    )
    (net (code "26") (name "Net-(EPD_C2-Pad2)") (class "Default")
      (node (ref "EPD_C2") (pin "2") (pinfunction "2_2") (pintype "passive"))
      (node (ref "J1") (pin "5") (pinfunction "5_5") (pintype "bidirectional"))
    )
    (net (code "27") (name "Net-(EPD_C5-Pad2)") (class "Default")
      (node (ref "EPD_C5") (pin "2") (pinfunction "2_2") (pintype "passive"))
      (node (ref "J1") (pin "15") (pinfunction "15_15") (pintype "bidirectional"))
    )
    (net (code "28") (name "Net-(EPD_C6-Pad2)") (class "Default")
      (node (ref "EPD_C6") (pin "2") (pinfunction "2_2") (pintype "passive"))
      (node (ref "J1") (pin "18") (pinfunction "18_18") (pintype "bidirectional"))
    )
    (net (code "29") (name "Net-(EPD_C7-Pad2)") (class "Default")
      (node (ref "EPD_C7") (pin "2") (pinfunction "2_2") (pintype "passive"))
      (node (ref "J1") (pin "19") (pinfunction "19_19") (pintype "bidirectional"))
    )
    (net (code "30") (name "Net-(EPD_C8-Pad2)") (class "Default")
      (node (ref "EPD_C8") (pin "2") (pinfunction "2_2") (pintype "passive"))
      (node (ref "J1") (pin "20") (pinfunction "20_20") (pintype "bidirectional"))
    )
    (net (code "31") (name "Net-(EPD_C9-Pad2)") (class "Default")
      (node (ref "EPD_C9") (pin "2") (pinfunction "2_2") (pintype "passive"))
      (node (ref "J1") (pin "21") (pinfunction "21_21") (pintype "bidirectional"))
    )
    (net (code "32") (name "Net-(EPD_C10-Pad2)") (class "Default")
      (node (ref "EPD_C10") (pin "2") (pinfunction "2_2") (pintype "passive"))
      (node (ref "J1") (pin "22") (pinfunction "22_22") (pintype "bidirectional"))
    )
    (net (code "33") (name "Net-(EPD_C12-Pad2)") (class "Default")
      (node (ref "EPD_C12") (pin "2") (pinfunction "2_2") (pintype "passive"))
      (node (ref "J1") (pin "24") (pinfunction "24_24") (pintype "bidirectional"))
    )
    (net (code "34") (name "Net-(IC2-CT)") (class "Default")
      (node (ref "C_DELAY") (pin "1") (pinfunction "1_1") (pintype "passive"))
      (node (ref "IC2") (pin "5") (pinfunction "CT_5") (pintype "bidirectional"))
    )
    (net (code "35") (name "Net-(J2-PadA5)") (class "Default")
      (node (ref "J2") (pin "A5") (pinfunction "A5_A5") (pintype "bidirectional"))
      (node (ref "R2-USB1") (pin "1") (pinfunction "1_1") (pintype "passive"))
    )
    (net (code "36") (name "Net-(J2-PadB5)") (class "Default")
      (node (ref "J2") (pin "B5") (pinfunction "B5_B5") (pintype "bidirectional"))
      (node (ref "R2-USB") (pin "1") (pinfunction "1_1") (pintype "passive"))
    )
    (net (code "37") (name "Net-(MCP73831-PROG)") (class "Default")
      (node (ref "MCP73831") (pin "5") (pinfunction "PROG_5") (pintype "input"))
      (node (ref "R2_BAT") (pin "2") (pinfunction "2_2") (pintype "passive"))
    )
    (net (code "38") (name "Net-(MCP73831-STAT)") (class "Default")
      (node (ref "MCP73831") (pin "1") (pinfunction "STAT_1") (pintype "output"))
      (node (ref "R1_BAT") (pin "1") (pinfunction "1_1") (pintype "passive"))
    )
    (net (code "39") (name "PREVGH") (class "Default")
      (node (ref "D5") (pin "1") (pinfunction "K_1") (pintype "bidirectional"))
    )
    (net (code "40") (name "PREVGL") (class "Default")
      (node (ref "D4") (pin "2") (pinfunction "A_2") (pintype "bidirectional"))
    )
    (net (code "41") (name "RESE") (class "Default")
      (node (ref "J1") (pin "3") (pinfunction "3_3") (pintype "bidirectional"))
      (node (ref "Q3") (pin "2") (pinfunction "S_2") (pintype "bidirectional"))
      (node (ref "R3") (pin "1") (pinfunction "1_1") (pintype "passive"))
    )
    (net (code "42") (name "RESET") (class "Default")
      (node (ref "C5") (pin "1") (pinfunction "1_1") (pintype "passive"))
      (node (ref "IC2") (pin "1") (pinfunction "VOUT_1") (pintype "bidirectional"))
      (node (ref "RESET_BUTTON") (pin "3") (pinfunction "3_3") (pintype "passive"))
      (node (ref "RESET_BUTTON") (pin "4") (pinfunction "4_4") (pintype "passive"))
      (node (ref "R_RESET") (pin "2") (pinfunction "2_2") (pintype "passive"))
      (node (ref "U2") (pin "3") (pinfunction "EN_3") (pintype "input"))
    )
    (net (code "43") (name "RESE`") (class "Default")
      (node (ref "R2") (pin "2") (pinfunction "2_2") (pintype "passive"))
      (node (ref "R3") (pin "2") (pinfunction "2_2") (pintype "passive"))
      (node (ref "SJ1") (pin "2") (pinfunction "2_2") (pintype "passive"))
    )
    (net (code "44") (name "RTC_RST") (class "Default")
      (node (ref "U2") (pin "16") (pinfunction "IO18_16") (pintype "bidirectional"))
      (node (ref "U3") (pin "4") (pinfunction "~{RST}_4") (pintype "input"))
    )
    (net (code "45") (name "RX") (class "Default")
      (node (ref "TP2") (pin "TP") (pinfunction "TP_TP") (pintype "input"))
      (node (ref "U2") (pin "24") (pinfunction "RXD0/GPIO17_24") (pintype "bidirectional"))
    )
    (net (code "46") (name "SCK") (class "Default")
      (node (ref "D10") (pin "1") (pinfunction "1_1") (pintype "passive"))
      (node (ref "J1") (pin "13") (pinfunction "13_13") (pintype "bidirectional"))
      (node (ref "J4") (pin "P5") (pinfunction "CLK_P5") (pintype "bidirectional"))
      (node (ref "R6") (pin "1") (pinfunction "1_1") (pintype "passive"))
      (node (ref "TP8") (pin "TP") (pinfunction "TP_TP") (pintype "input"))
      (node (ref "U1") (pin "6") (pinfunction "CLK_6") (pintype "input"))
      (node (ref "U2") (pin "6") (pinfunction "IO6_6") (pintype "bidirectional"))
    )
    (net (code "47") (name "SCL") (class "Default")
      (node (ref "J3") (pin "4") (pinfunction "4_4") (pintype "passive"))
      (node (ref "R2-PINH") (pin "1") (pinfunction "1_1") (pintype "passive"))
      (node (ref "SENSOR2") (pin "4") (pinfunction "SCK_4") (pintype "input"))
      (node (ref "U2") (pin "20") (pinfunction "IO22_20") (pintype "bidirectional"))
      (node (ref "U3") (pin "16") (pinfunction "SCL_16") (pintype "input"))
      (node (ref "U4") (pin "7") (pinfunction "SCL_7") (pintype "input"))
    )
    (net (code "48") (name "SDA") (class "Default")
      (node (ref "J3") (pin "3") (pinfunction "3_3") (pintype "passive"))
      (node (ref "R1_PINH") (pin "1") (pinfunction "1_1") (pintype "passive"))
      (node (ref "SENSOR2") (pin "3") (pinfunction "SDI_3") (pintype "bidirectional"))
      (node (ref "U2") (pin "19") (pinfunction "IO21_19") (pintype "bidirectional"))
      (node (ref "U3") (pin "15") (pinfunction "SDA_15") (pintype "bidirectional"))
      (node (ref "U4") (pin "8") (pinfunction "SDA_8") (pintype "bidirectional"))
    )
    (net (code "49") (name "SRC") (class "Default")
      (node (ref "C4") (pin "2") (pinfunction "2_2") (pintype "passive"))
      (node (ref "D5") (pin "2") (pinfunction "A_2") (pintype "bidirectional"))
      (node (ref "L1") (pin "1") (pinfunction "1_1") (pintype "passive"))
      (node (ref "Q3") (pin "3") (pinfunction "D_3") (pintype "bidirectional"))
    )
    (net (code "50") (name "SS_SD") (class "Default")
      (node (ref "D8") (pin "1") (pinfunction "1_1") (pintype "passive"))
      (node (ref "J4") (pin "P2") (pinfunction "CD/DAT3_P2") (pintype "bidirectional"))
      (node (ref "R10") (pin "1") (pinfunction "1_1") (pintype "passive"))
      (node (ref "U2") (pin "4") (pinfunction "IO4_4") (pintype "bidirectional"))
    )
    (net (code "51") (name "TX") (class "Default")
      (node (ref "TP1") (pin "TP") (pinfunction "TP_TP") (pintype "input"))
      (node (ref "U2") (pin "25") (pinfunction "TXD0/GPIO16_25") (pintype "bidirectional"))
    )
    (net (code "52") (name "USB_D+") (class "Default")
      (node (ref "D1") (pin "4") (pinfunction "I/O2_2_4") (pintype "bidirectional"))
      (node (ref "U2") (pin "14") (pinfunction "IO13_14") (pintype "bidirectional"))
    )
    (net (code "53") (name "USB_D-") (class "Default")
      (node (ref "D1") (pin "6") (pinfunction "I/O1_2_6") (pintype "bidirectional"))
      (node (ref "U2") (pin "13") (pinfunction "IO12_13") (pintype "bidirectional"))
    )
    (net (code "54") (name "VBAT") (class "Default")
      (node (ref "C2_BAT") (pin "1") (pinfunction "1_1") (pintype "passive"))
      (node (ref "MCP73831") (pin "3") (pinfunction "VBAT_3") (pintype "power_in"))
      (node (ref "Q1") (pin "3") (pinfunction "D_3") (pintype "bidirectional"))
      (node (ref "TP3") (pin "TP") (pinfunction "TP_TP") (pintype "input"))
      (node (ref "U4") (pin "2") (pinfunction "CELL_2") (pintype "power_in"))
      (node (ref "U4") (pin "3") (pinfunction "VDD_3") (pintype "power_in"))
    )
    (net (code "55") (name "VBUS") (class "Default")
      (node (ref "C1_BAT") (pin "1") (pinfunction "1_1") (pintype "passive"))
      (node (ref "C4_USB") (pin "1") (pinfunction "1_1") (pintype "passive"))
      (node (ref "C5_USB") (pin "1") (pinfunction "1_1") (pintype "passive"))
      (node (ref "CHG_LED") (pin "A") (pinfunction "A_A") (pintype "passive"))
      (node (ref "D1") (pin "2") (pinfunction "GND_2") (pintype "bidirectional"))
      (node (ref "D2") (pin "2") (pinfunction "ANODE_2") (pintype "bidirectional"))
      (node (ref "MCP73831") (pin "4") (pinfunction "VIN_4") (pintype "power_in"))
      (node (ref "PFMF.050.1") (pin "2") (pinfunction "2_2") (pintype "passive"))
      (node (ref "Q1") (pin "1") (pinfunction "G_1") (pintype "bidirectional"))
      (node (ref "R1_PWRUSB") (pin "2") (pinfunction "2_2") (pintype "passive"))
      (node (ref "TP14") (pin "TP") (pinfunction "TP_TP") (pintype "input"))
    )
    (net (code "56") (name "VRTC") (class "Default")
      (node (ref "C10_SUPERCAP") (pin "2") (pinfunction "2_2") (pintype "passive"))
      (node (ref "C8") (pin "1") (pinfunction "1_1") (pintype "passive"))
      (node (ref "R_CAPACITOR") (pin "2") (pinfunction "2_2") (pintype "passive"))
      (node (ref "U3") (pin "14") (pinfunction "VBAT_14") (pintype "power_in"))
    )
    (net (code "57") (name "VUSB") (class "Default")
      (node (ref "J2") (pin "A4") (pinfunction "A4_A4") (pintype "bidirectional"))
      (node (ref "J2") (pin "A9") (pinfunction "A9_A9") (pintype "bidirectional"))
      (node (ref "J2") (pin "B4") (pinfunction "B4_B4") (pintype "bidirectional"))
      (node (ref "J2") (pin "B9") (pinfunction "B9_B9") (pintype "bidirectional"))
      (node (ref "PFMF.050.1") (pin "1") (pinfunction "1_1") (pintype "passive"))
    )
    (net (code "58") (name "unconnected-(IC2-NC-Pad4)") (class "Default")
      (node (ref "IC2") (pin "4") (pinfunction "NC_4") (pintype "no_connect"))
    )
    (net (code "59") (name "unconnected-(IC4-NC-Pad4)") (class "Default")
      (node (ref "IC4") (pin "4") (pinfunction "NC_4") (pintype "no_connect"))
    )
    (net (code "60") (name "unconnected-(J1-Pad1)") (class "Default")
      (node (ref "J1") (pin "1") (pinfunction "1_1") (pintype "bidirectional"))
    )
    (net (code "61") (name "unconnected-(J1-Pad6)") (class "Default")
      (node (ref "J1") (pin "6") (pinfunction "6_6") (pintype "bidirectional"))
    )
    (net (code "62") (name "unconnected-(J1-Pad7)") (class "Default")
      (node (ref "J1") (pin "7") (pinfunction "7_7") (pintype "bidirectional"))
    )
    (net (code "63") (name "unconnected-(J2-PadA8)") (class "Default")
      (node (ref "J2") (pin "A8") (pinfunction "A8_A8") (pintype "bidirectional"))
    )
    (net (code "64") (name "unconnected-(J2-PadB8)") (class "Default")
      (node (ref "J2") (pin "B8") (pinfunction "B8_B8") (pintype "bidirectional"))
    )
    (net (code "65") (name "unconnected-(J4-DAT1-PadP8)") (class "Default")
      (node (ref "J4") (pin "P8") (pinfunction "DAT1_P8") (pintype "bidirectional"))
    )
    (net (code "66") (name "unconnected-(J4-DAT2-PadP1)") (class "Default")
      (node (ref "J4") (pin "P1") (pinfunction "DAT2_P1") (pintype "bidirectional"))
    )
    (net (code "67") (name "unconnected-(J4-DETECTION_1-PadS1)") (class "Default")
      (node (ref "J4") (pin "S1") (pinfunction "DETECTION_1_S1") (pintype "bidirectional"))
    )
    (net (code "68") (name "unconnected-(J4-DETECTION_2-PadS2)") (class "Default")
      (node (ref "J4") (pin "S2") (pinfunction "DETECTION_2_S2") (pintype "bidirectional"))
    )
    (net (code "69") (name "unconnected-(U2-NC-Pad22)") (class "Default")
      (node (ref "U2") (pin "22") (pinfunction "NC_22") (pintype "no_connect"))
    )
    (net (code "70") (name "unconnected-(U4-~{ALERT}-Pad5)") (class "Default")
      (node (ref "U4") (pin "5") (pinfunction "~{ALERT}_5") (pintype "output"))
    )
  )
)
